# Pi1541_Switch.net
KiCad netlist of a schematic drawn in EAGLE
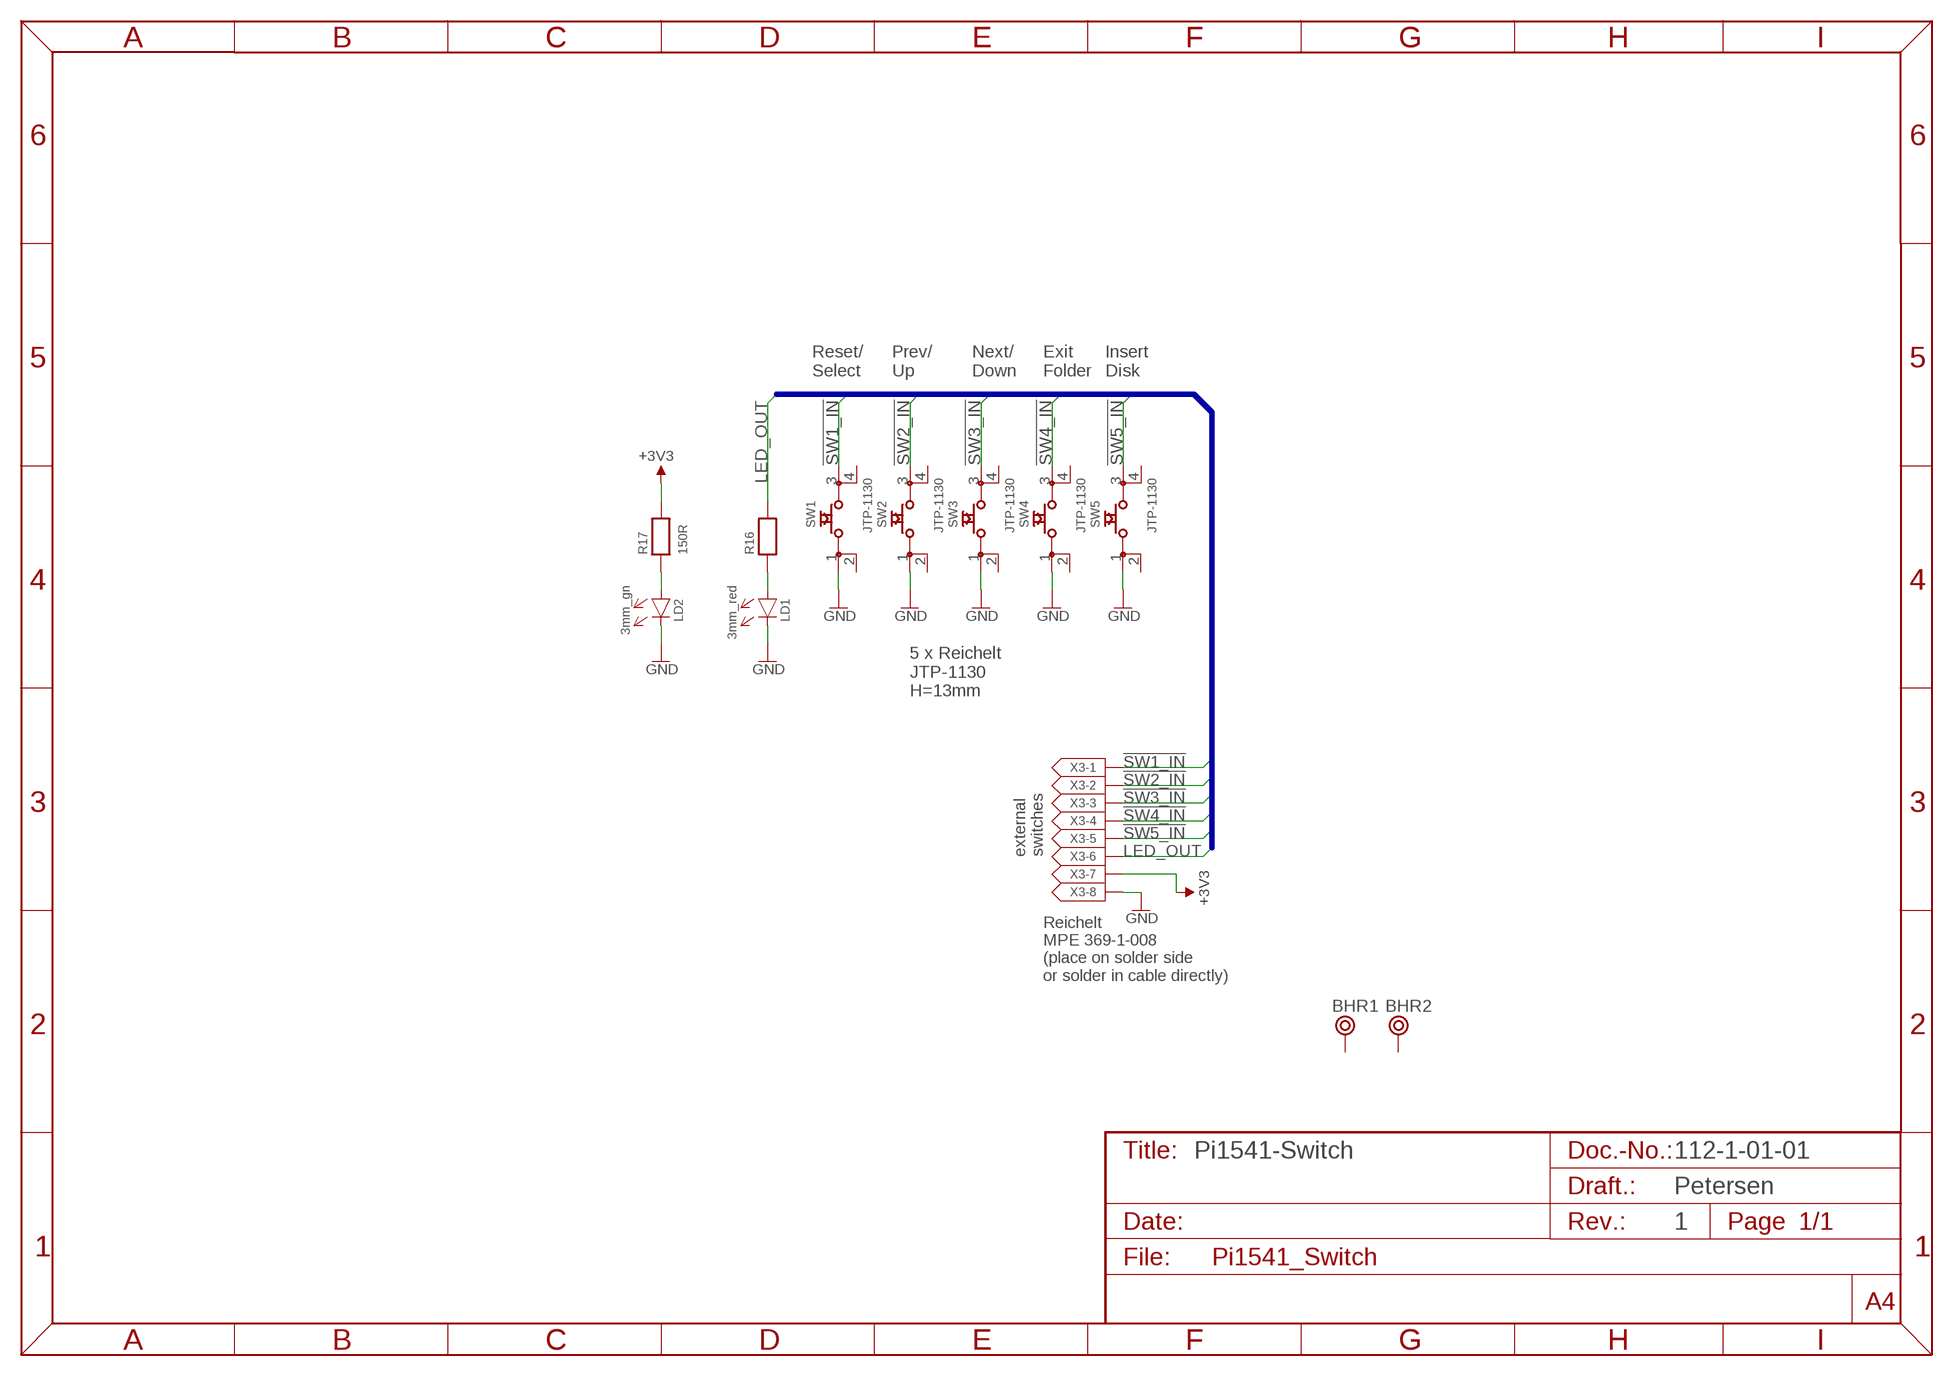
[diagram p0: schematic, sheet 1]

(export (version "E")
  (design (tool "Eeschema 10.0.6"))
  (components
    (comp (ref "BHR1")
      (value "BOHR2,8")
      (footprint "eagle-import:BOHR2,8_")
      (libsource (lib "eagle-import") (part "BOHR2,8"))
    )
    (comp (ref "BHR2")
      (value "BOHR2,8")
      (footprint "eagle-import:BOHR2,8_")
      (libsource (lib "eagle-import") (part "BOHR2,8"))
    )
    (comp (ref "LD1")
      (value "3mm_red")
      (footprint "eagle-import:3MM")
      (libsource (lib "eagle-import") (part "3MM"))
    )
    (comp (ref "LD2")
      (value "3mm_gn")
      (footprint "eagle-import:3MM")
      (libsource (lib "eagle-import") (part "3MM"))
    )
    (comp (ref "R16")
      (value "150R")
      (footprint "eagle-import:0805")
      (libsource (lib "eagle-import") (part "R-0805"))
    )
    (comp (ref "R17")
      (value "150R")
      (footprint "eagle-import:0805")
      (libsource (lib "eagle-import") (part "R-0805"))
    )
    (comp (ref "SW1")
      (value "JTP-1130")
      (footprint "eagle-import:JTP-1130")
      (libsource (lib "eagle-import") (part "JTP-1130"))
    )
    (comp (ref "SW2")
      (value "JTP-1130")
      (footprint "eagle-import:JTP-1130")
      (libsource (lib "eagle-import") (part "JTP-1130"))
    )
    (comp (ref "SW3")
      (value "JTP-1130")
      (footprint "eagle-import:JTP-1130")
      (libsource (lib "eagle-import") (part "JTP-1130"))
    )
    (comp (ref "SW4")
      (value "JTP-1130")
      (footprint "eagle-import:JTP-1130")
      (libsource (lib "eagle-import") (part "JTP-1130"))
    )
    (comp (ref "SW5")
      (value "JTP-1130")
      (footprint "eagle-import:JTP-1130")
      (libsource (lib "eagle-import") (part "JTP-1130"))
    )
    (comp (ref "X3")
      (value "MICMA08B")
      (footprint "eagle-import:MICMA08B")
      (libsource (lib "eagle-import") (part "MICMA08B"))
    )
  )
  (nets
    (net (code "1") (name "+3V3") (class "Default")
      (node (ref "R17") (pin "2") (pinfunction "2_2") (pintype "passive"))
      (node (ref "X3") (pin "7") (pinfunction "1_7") (pintype "bidirectional"))
    )
    (net (code "2") (name "/LED_OUT") (class "Default")
      (node (ref "R16") (pin "2") (pinfunction "2_2") (pintype "passive"))
      (node (ref "X3") (pin "6") (pinfunction "1_6") (pintype "bidirectional"))
    )
    (net (code "3") (name "/~{SW1_IN}") (class "Default")
      (node (ref "SW1") (pin "3") (pinfunction "3_3") (pintype "passive"))
      (node (ref "X3") (pin "1") (pinfunction "1_1") (pintype "bidirectional"))
    )
    (net (code "4") (name "/~{SW2_IN}") (class "Default")
      (node (ref "SW2") (pin "3") (pinfunction "3_3") (pintype "passive"))
      (node (ref "X3") (pin "2") (pinfunction "1_2") (pintype "bidirectional"))
    )
    (net (code "5") (name "/~{SW3_IN}") (class "Default")
      (node (ref "SW3") (pin "3") (pinfunction "3_3") (pintype "passive"))
      (node (ref "X3") (pin "3") (pinfunction "1_3") (pintype "bidirectional"))
    )
    (net (code "6") (name "/~{SW4_IN}") (class "Default")
      (node (ref "SW4") (pin "3") (pinfunction "3_3") (pintype "passive"))
      (node (ref "X3") (pin "4") (pinfunction "1_4") (pintype "bidirectional"))
    )
    (net (code "7") (name "/~{SW5_IN}") (class "Default")
      (node (ref "SW5") (pin "3") (pinfunction "3_3") (pintype "passive"))
      (node (ref "X3") (pin "5") (pinfunction "1_5") (pintype "bidirectional"))
    )
    (net (code "8") (name "GND") (class "Default")
      (node (ref "LD1") (pin "K") (pinfunction "K_K") (pintype "bidirectional"))
      (node (ref "LD2") (pin "K") (pinfunction "K_K") (pintype "bidirectional"))
      (node (ref "SW1") (pin "1") (pinfunction "1_1") (pintype "passive"))
      (node (ref "SW2") (pin "1") (pinfunction "1_1") (pintype "passive"))
      (node (ref "SW3") (pin "1") (pinfunction "1_1") (pintype "passive"))
      (node (ref "SW4") (pin "1") (pinfunction "1_1") (pintype "passive"))
      (node (ref "SW5") (pin "1") (pinfunction "1_1") (pintype "passive"))
      (node (ref "X3") (pin "8") (pinfunction "1_8") (pintype "bidirectional"))
    )
    (net (code "9") (name "Net-(LD1-PadA)") (class "Default")
      (node (ref "LD1") (pin "A") (pinfunction "A_A") (pintype "bidirectional"))
      (node (ref "R16") (pin "1") (pinfunction "1_1") (pintype "passive"))
    )
    (net (code "10") (name "Net-(LD2-PadA)") (class "Default")
      (node (ref "LD2") (pin "A") (pinfunction "A_A") (pintype "bidirectional"))
      (node (ref "R17") (pin "1") (pinfunction "1_1") (pintype "passive"))
    )
    (net (code "11") (name "unconnected-(BHR1-PadP$1)") (class "Default")
      (node (ref "BHR1") (pin "P$1") (pinfunction "P$1_P$1") (pintype "passive"))
    )
    (net (code "12") (name "unconnected-(BHR2-PadP$1)") (class "Default")
      (node (ref "BHR2") (pin "P$1") (pinfunction "P$1_P$1") (pintype "passive"))
    )
    (net (code "13") (name "unconnected-(SW1-Pad2)") (class "Default")
      (node (ref "SW1") (pin "2") (pinfunction "2_2") (pintype "passive"))
    )
    (net (code "14") (name "unconnected-(SW1-Pad4)") (class "Default")
      (node (ref "SW1") (pin "4") (pinfunction "4_4") (pintype "passive"))
    )
    (net (code "15") (name "unconnected-(SW2-Pad2)") (class "Default")
      (node (ref "SW2") (pin "2") (pinfunction "2_2") (pintype "passive"))
    )
    (net (code "16") (name "unconnected-(SW2-Pad4)") (class "Default")
      (node (ref "SW2") (pin "4") (pinfunction "4_4") (pintype "passive"))
    )
    (net (code "17") (name "unconnected-(SW3-Pad2)") (class "Default")
      (node (ref "SW3") (pin "2") (pinfunction "2_2") (pintype "passive"))
    )
    (net (code "18") (name "unconnected-(SW3-Pad4)") (class "Default")
      (node (ref "SW3") (pin "4") (pinfunction "4_4") (pintype "passive"))
    )
    (net (code "19") (name "unconnected-(SW4-Pad2)") (class "Default")
      (node (ref "SW4") (pin "2") (pinfunction "2_2") (pintype "passive"))
    )
    (net (code "20") (name "unconnected-(SW4-Pad4)") (class "Default")
      (node (ref "SW4") (pin "4") (pinfunction "4_4") (pintype "passive"))
    )
    (net (code "21") (name "unconnected-(SW5-Pad2)") (class "Default")
      (node (ref "SW5") (pin "2") (pinfunction "2_2") (pintype "passive"))
    )
    (net (code "22") (name "unconnected-(SW5-Pad4)") (class "Default")
      (node (ref "SW5") (pin "4") (pinfunction "4_4") (pintype "passive"))
    )
  )
)
